# laminadora.net
KiCad netlist of a schematic drawn in EAGLE
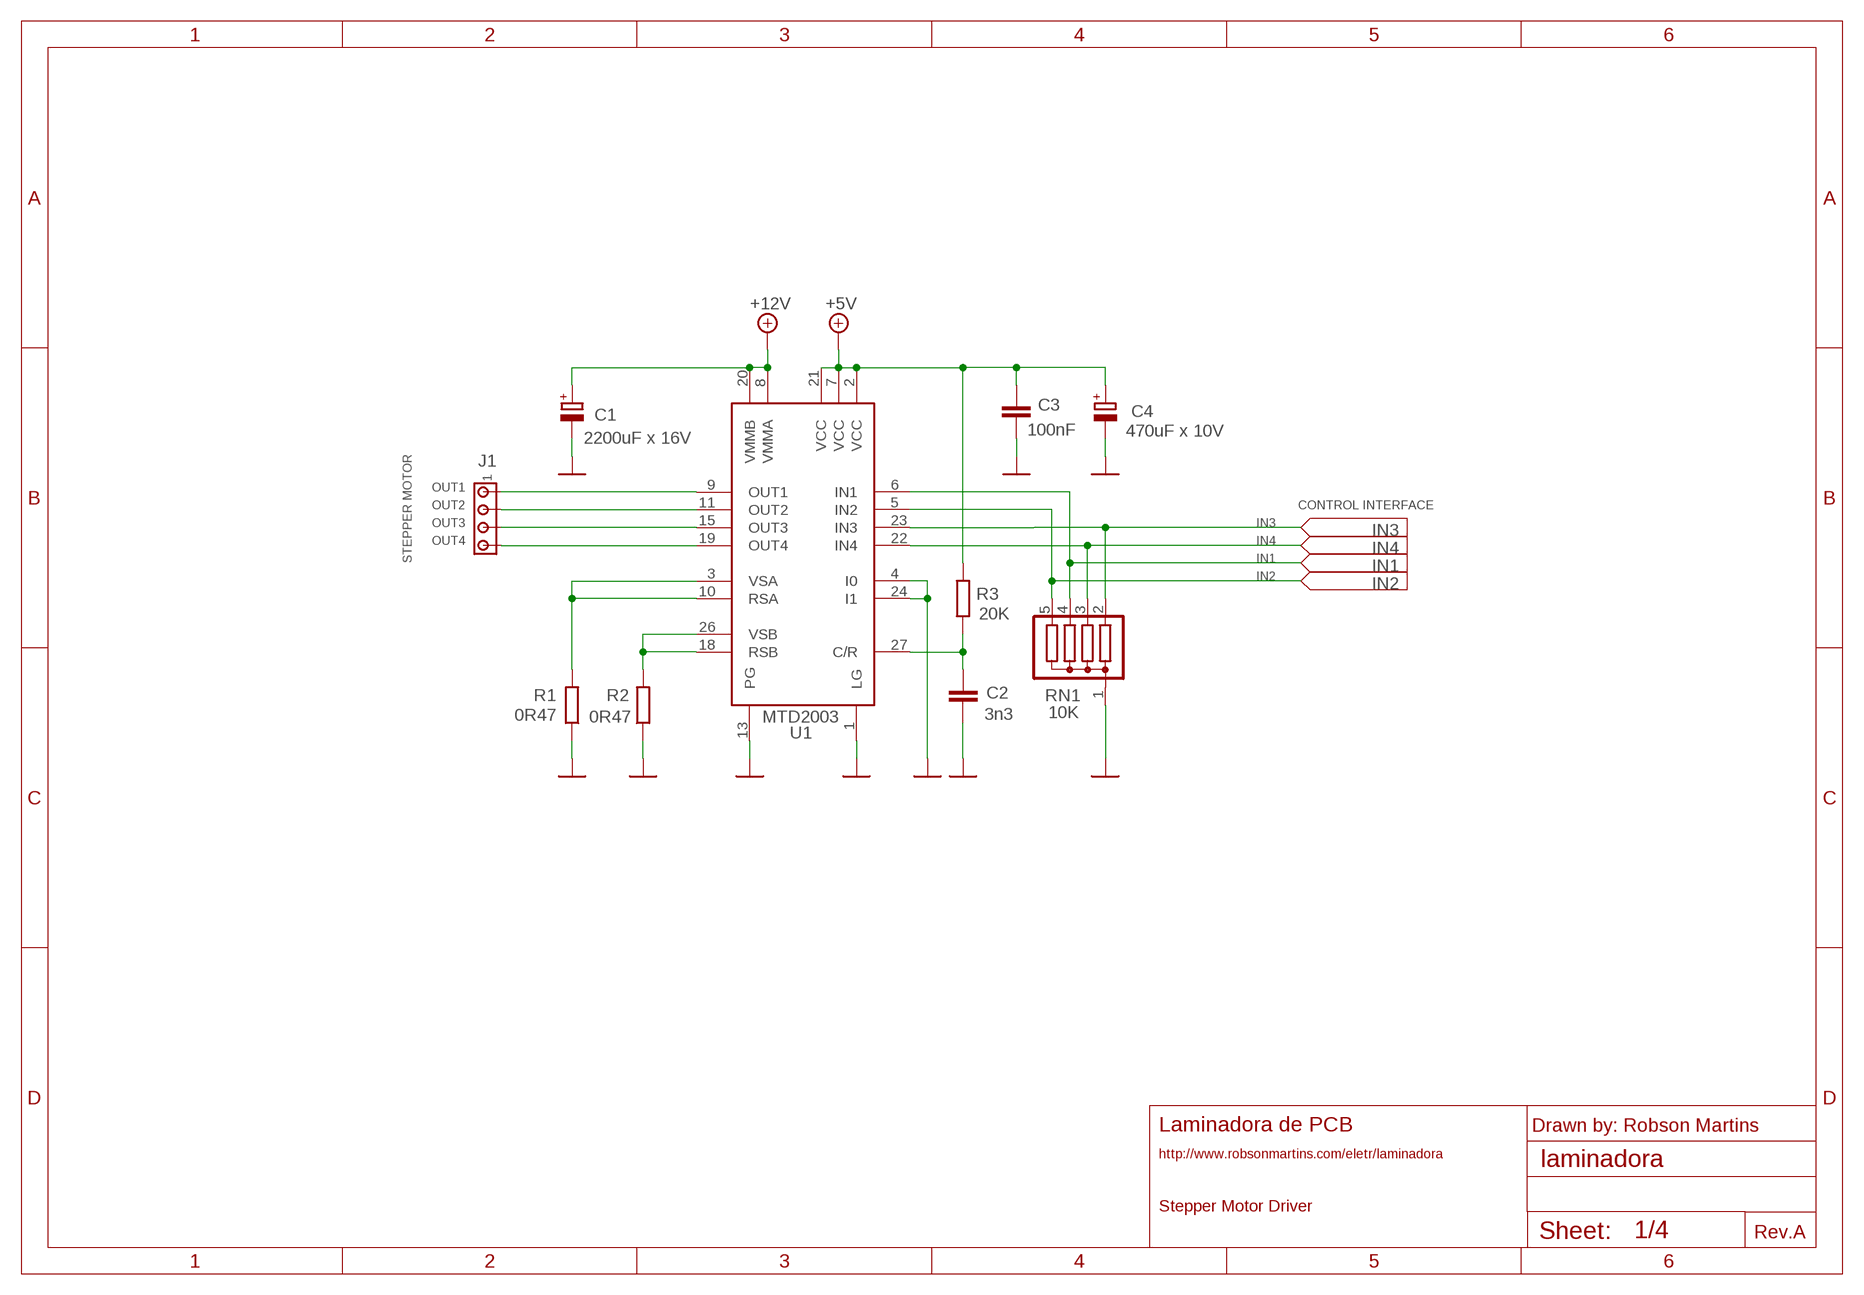
[diagram p0: schematic, sheet 1]
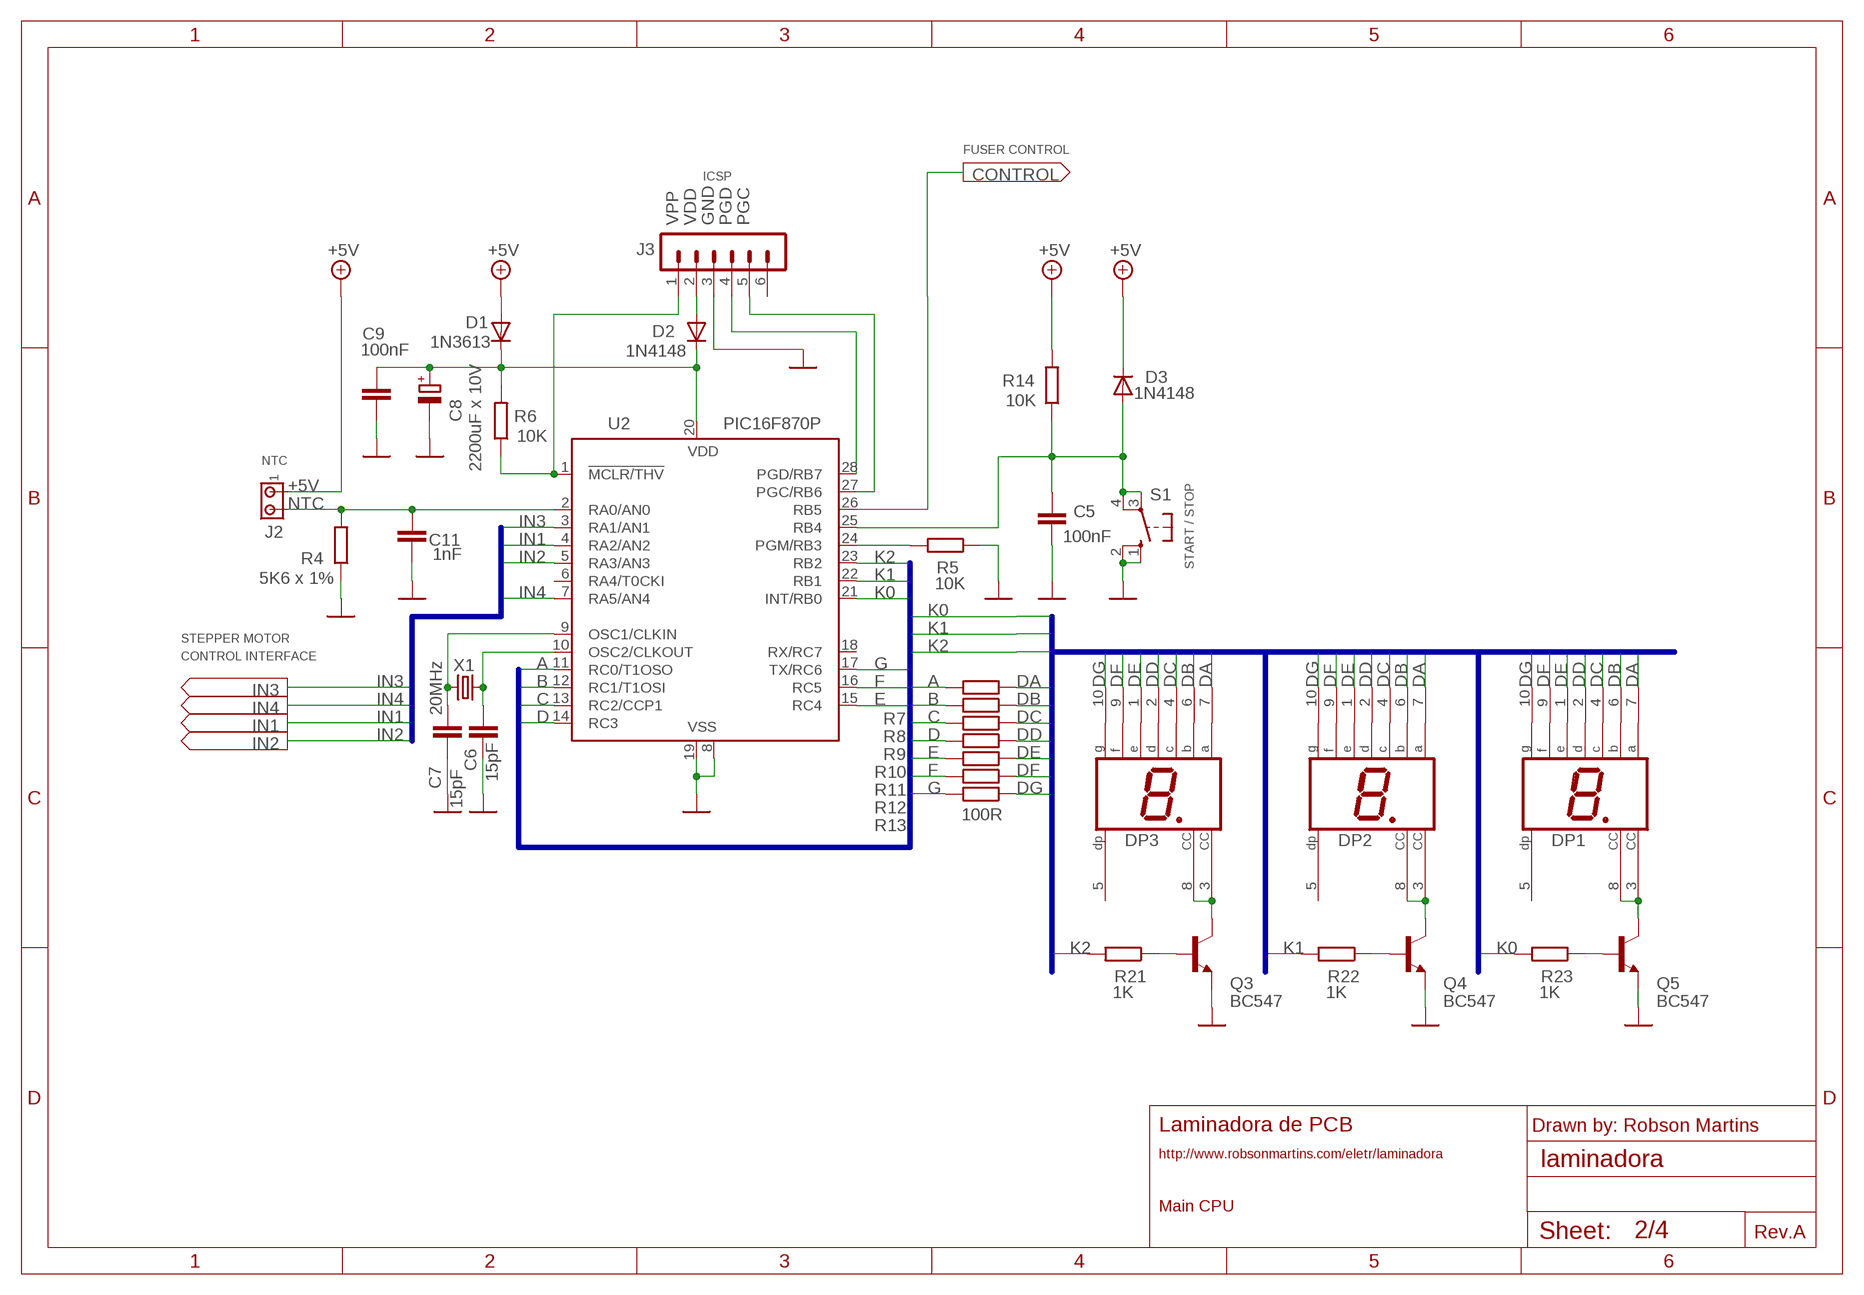
[diagram p1: schematic, sheet 2]
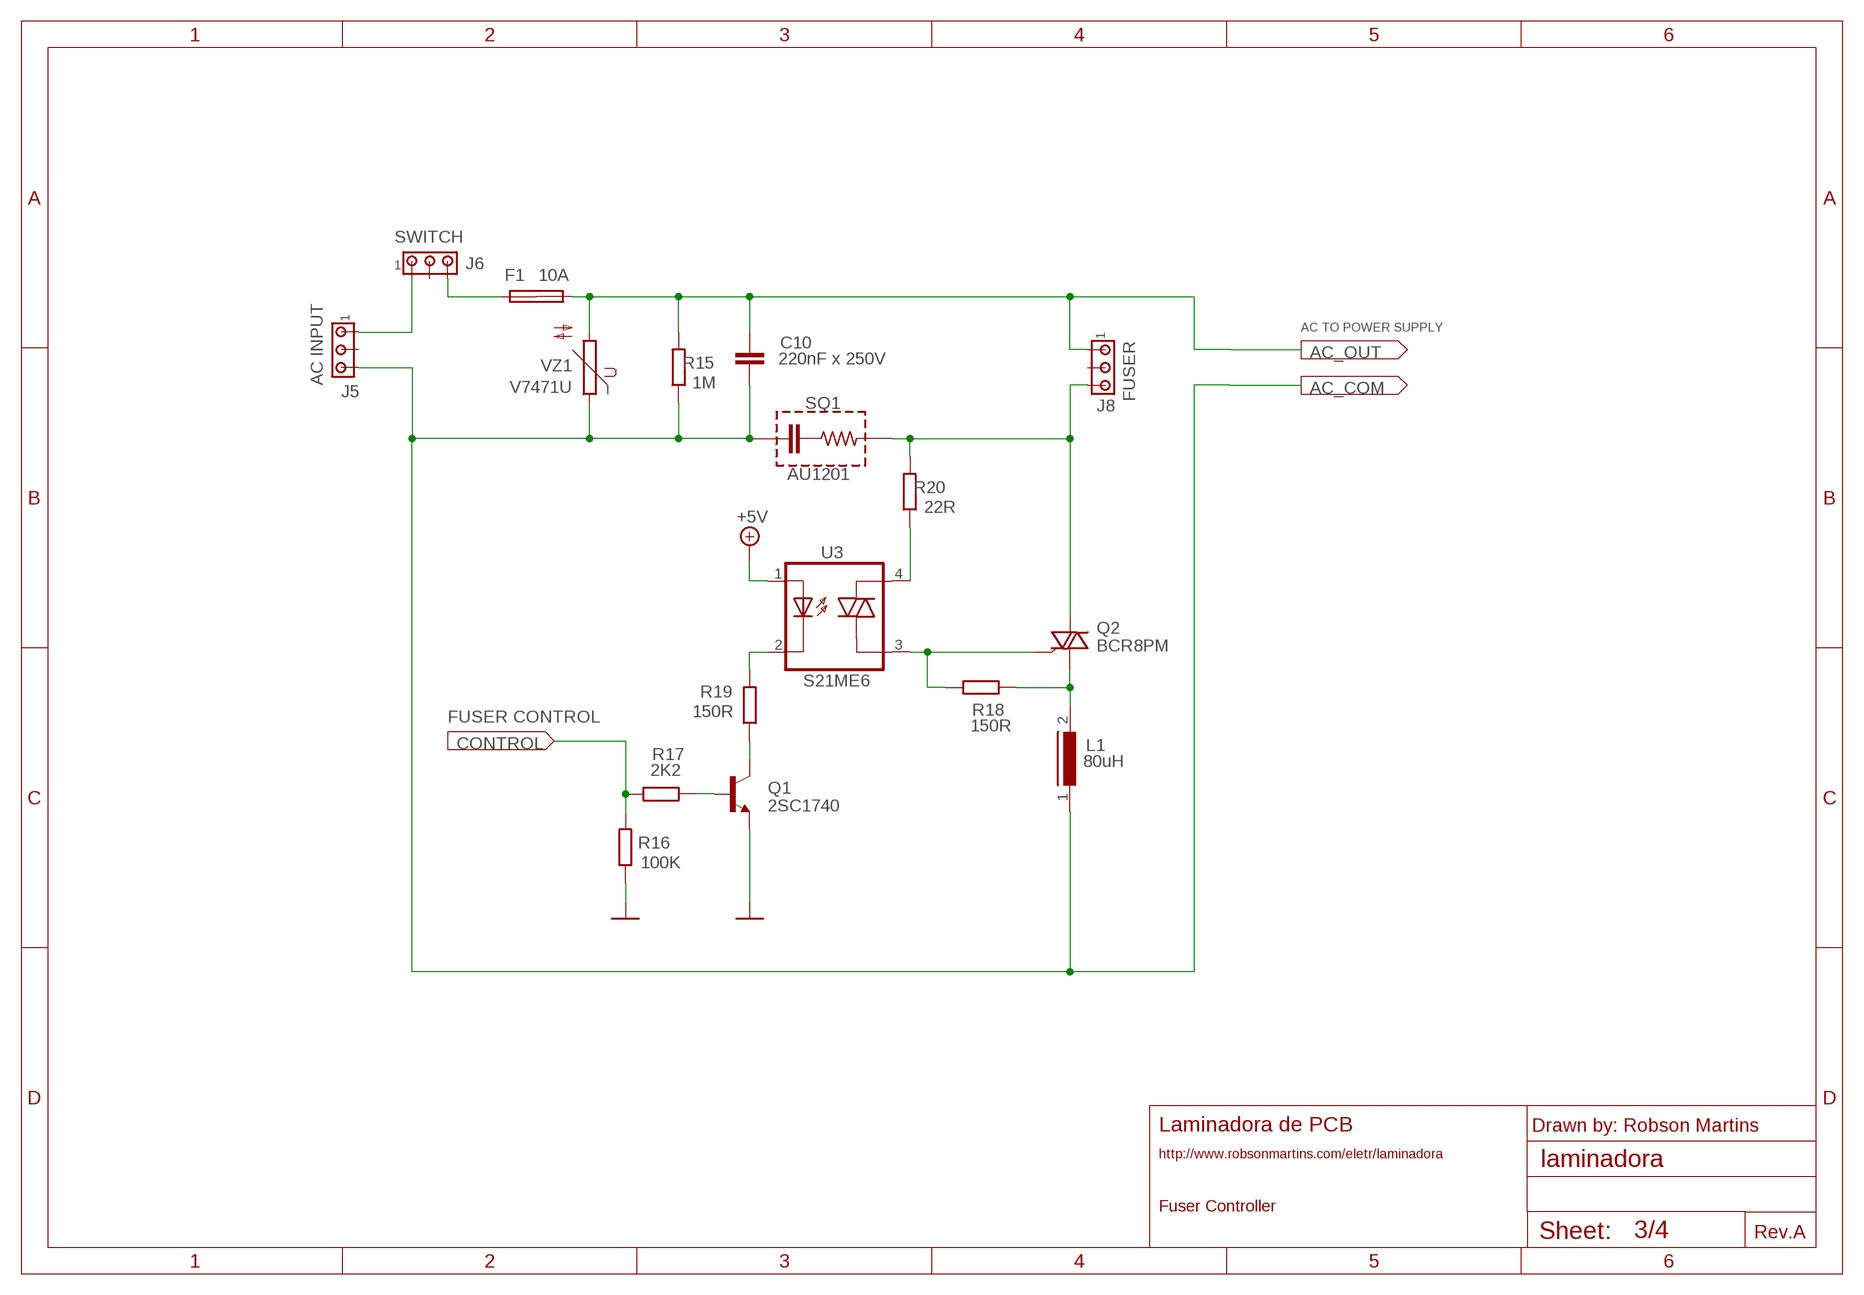
[diagram p2: schematic, sheet 3]
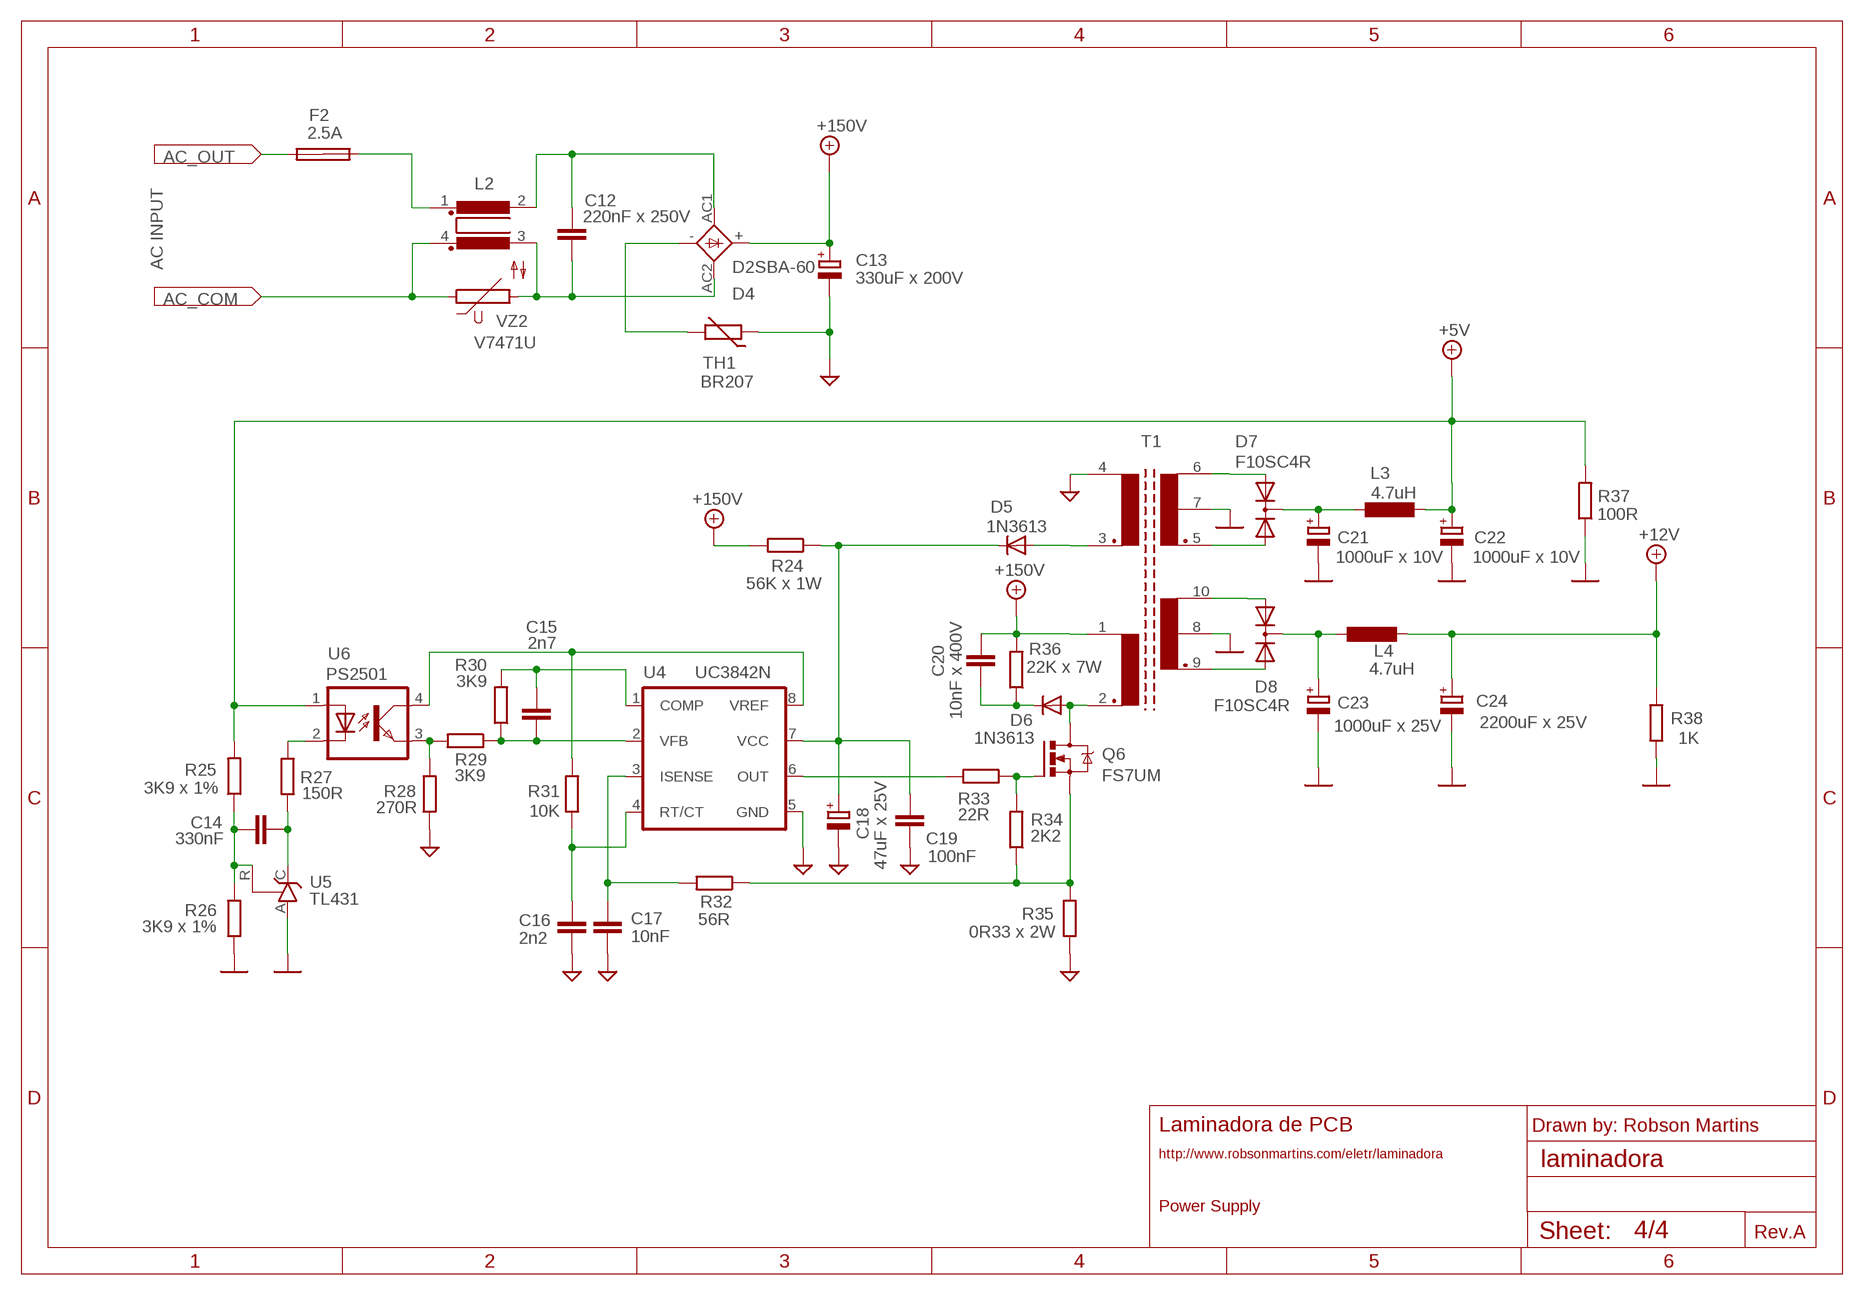
[diagram p3: schematic, sheet 4]

(export (version "E")
  (design (tool "Eeschema 10.0.6"))
  (components
    (comp (ref "C5")
      (value "100nF")
      (footprint "eagle-import:C050-025X075")
      (libsource (lib "eagle-import") (part "C-EU050-025X075"))
    )
    (comp (ref "C6")
      (value "15pF")
      (footprint "eagle-import:C025-025X050")
      (libsource (lib "eagle-import") (part "C-EU025-025X050"))
    )
    (comp (ref "C7")
      (value "15pF")
      (footprint "eagle-import:C025-025X050")
      (libsource (lib "eagle-import") (part "C-EU025-025X050"))
    )
    (comp (ref "C8")
      (value "2200uF x 10V")
      (footprint "eagle-import:E5-13")
      (libsource (lib "eagle-import") (part "CPOL-EUE5-13"))
    )
    (comp (ref "C9")
      (value "100nF")
      (footprint "eagle-import:C050-025X075")
      (libsource (lib "eagle-import") (part "C-EU050-025X075"))
    )
    (comp (ref "C11")
      (value "1nF")
      (footprint "eagle-import:C025-025X050")
      (libsource (lib "eagle-import") (part "C-EU025-025X050"))
    )
    (comp (ref "D1")
      (value "1N3613")
      (footprint "eagle-import:DO35-7")
      (libsource (lib "eagle-import") (part "1N4148DO35-7"))
    )
    (comp (ref "D2")
      (value "1N4148")
      (footprint "eagle-import:DO35-7")
      (libsource (lib "eagle-import") (part "1N4148DO35-7"))
    )
    (comp (ref "D3")
      (value "1N4148")
      (footprint "eagle-import:DO35-7")
      (libsource (lib "eagle-import") (part "1N4148DO35-7"))
    )
    (comp (ref "DP1")
      (value "HD-H103")
      (footprint "eagle-import:HDSP-M")
      (libsource (lib "eagle-import") (part "HD-H103"))
    )
    (comp (ref "DP2")
      (value "HD-H103")
      (footprint "eagle-import:HDSP-M")
      (libsource (lib "eagle-import") (part "HD-H103"))
    )
    (comp (ref "DP3")
      (value "HD-H103")
      (footprint "eagle-import:HDSP-M")
      (libsource (lib "eagle-import") (part "HD-H103"))
    )
    (comp (ref "J2")
      (value "A20-04")
      (footprint "eagle-import:10X02MTA")
      (libsource (lib "eagle-import") (part "MTA02-100"))
    )
    (comp (ref "J3")
      (value "MA06-1")
      (footprint "eagle-import:MA06-1")
      (libsource (lib "eagle-import") (part "MA06-1"))
    )
    (comp (ref "Q3")
      (value "BC547")
      (footprint "eagle-import:TO92")
      (libsource (lib "eagle-import") (part "BC547"))
    )
    (comp (ref "Q4")
      (value "BC547")
      (footprint "eagle-import:TO92")
      (libsource (lib "eagle-import") (part "BC547"))
    )
    (comp (ref "Q5")
      (value "BC547")
      (footprint "eagle-import:TO92")
      (libsource (lib "eagle-import") (part "BC547"))
    )
    (comp (ref "R4")
      (value "5K6 x 1%")
      (footprint "eagle-import:0207_10")
      (libsource (lib "eagle-import") (part "R-EU_0207/10"))
    )
    (comp (ref "R5")
      (value "10K")
      (footprint "eagle-import:0207_10")
      (libsource (lib "eagle-import") (part "R-EU_0207/10"))
    )
    (comp (ref "R6")
      (value "10K")
      (footprint "eagle-import:0207_10")
      (libsource (lib "eagle-import") (part "R-EU_0207/10"))
    )
    (comp (ref "R7")
      (value "100R")
      (footprint "eagle-import:0207_10")
      (libsource (lib "eagle-import") (part "R-EU_0207/10"))
    )
    (comp (ref "R8")
      (value "100R")
      (footprint "eagle-import:0207_10")
      (libsource (lib "eagle-import") (part "R-EU_0207/10"))
    )
    (comp (ref "R9")
      (value "100R")
      (footprint "eagle-import:0207_10")
      (libsource (lib "eagle-import") (part "R-EU_0207/10"))
    )
    (comp (ref "R10")
      (value "100R")
      (footprint "eagle-import:0207_10")
      (libsource (lib "eagle-import") (part "R-EU_0207/10"))
    )
    (comp (ref "R11")
      (value "100R")
      (footprint "eagle-import:0207_10")
      (libsource (lib "eagle-import") (part "R-EU_0207/10"))
    )
    (comp (ref "R12")
      (value "100R")
      (footprint "eagle-import:0207_10")
      (libsource (lib "eagle-import") (part "R-EU_0207/10"))
    )
    (comp (ref "R13")
      (value "100R")
      (footprint "eagle-import:0207_10")
      (libsource (lib "eagle-import") (part "R-EU_0207/10"))
    )
    (comp (ref "R14")
      (value "10K")
      (footprint "eagle-import:0207_10")
      (libsource (lib "eagle-import") (part "R-EU_0207/10"))
    )
    (comp (ref "R21")
      (value "1K")
      (footprint "eagle-import:0207_10")
      (libsource (lib "eagle-import") (part "R-EU_0207/10"))
    )
    (comp (ref "R22")
      (value "1K")
      (footprint "eagle-import:0207_10")
      (libsource (lib "eagle-import") (part "R-EU_0207/10"))
    )
    (comp (ref "R23")
      (value "1K")
      (footprint "eagle-import:0207_10")
      (libsource (lib "eagle-import") (part "R-EU_0207/10"))
    )
    (comp (ref "S1")
      (value "10-XX")
      (footprint "eagle-import:B3F-10XX")
      (fields (field (name "MPN") "B3F-1000"))
      (libsource (lib "eagle-import") (part "10-XX"))
    )
    (comp (ref "U2")
      (value "PIC16F870P")
      (footprint "eagle-import:DIL28-3")
      (fields (field (name "MF") "MICROCHIP") (field (name "MPN") "PIC16F870-I/SP"))
      (libsource (lib "eagle-import") (part "PIC16870PF"))
    )
    (comp (ref "X1")
      (value "20MHz")
      (footprint "eagle-import:HC49U-V")
      (libsource (lib "eagle-import") (part "CRYSTALHC49U-V"))
    )
    (comp (ref "C12")
      (value "220nF x 250V")
      (footprint "eagle-import:C225-108X268")
      (libsource (lib "eagle-import") (part "C-EU225-108X268"))
    )
    (comp (ref "C13")
      (value "330uF x 200V")
      (footprint "eagle-import:EB22,5D")
      (libsource (lib "eagle-import") (part "CPOL-EUE10-22.5"))
    )
    (comp (ref "C14")
      (value "330nF")
      (footprint "eagle-import:C075-042X103")
      (libsource (lib "eagle-import") (part "C-EU075-042X103"))
    )
    (comp (ref "C15")
      (value "2n7")
      (footprint "eagle-import:C050-030X075")
      (libsource (lib "eagle-import") (part "C-EU050-030X075"))
    )
    (comp (ref "C16")
      (value "2n2")
      (footprint "eagle-import:C050-030X075")
      (libsource (lib "eagle-import") (part "C-EU050-030X075"))
    )
    (comp (ref "C17")
      (value "10nF")
      (footprint "eagle-import:C050-030X075")
      (libsource (lib "eagle-import") (part "C-EU050-030X075"))
    )
    (comp (ref "C18")
      (value "47uF x 25V")
      (footprint "eagle-import:E5-6")
      (libsource (lib "eagle-import") (part "CPOL-EUE5-6"))
    )
    (comp (ref "C19")
      (value "100nF")
      (footprint "eagle-import:C050-030X075")
      (libsource (lib "eagle-import") (part "C-EU050-030X075"))
    )
    (comp (ref "C20")
      (value "10nF x 400V")
      (footprint "eagle-import:C102-043X133")
      (libsource (lib "eagle-import") (part "C-EU102-043X133"))
    )
    (comp (ref "C21")
      (value "1000uF x 10V")
      (footprint "eagle-import:E5-10,5")
      (libsource (lib "eagle-import") (part "CPOL-EUE5-10.5"))
    )
    (comp (ref "C22")
      (value "1000uF x 10V")
      (footprint "eagle-import:E5-10,5")
      (libsource (lib "eagle-import") (part "CPOL-EUE5-10.5"))
    )
    (comp (ref "C23")
      (value "1000uF x 25V")
      (footprint "eagle-import:E5-13")
      (libsource (lib "eagle-import") (part "CPOL-EUE5-13"))
    )
    (comp (ref "C24")
      (value "2200uF x 25V")
      (footprint "eagle-import:E5-13")
      (libsource (lib "eagle-import") (part "CPOL-EUE5-13"))
    )
    (comp (ref "D4")
      (value "D2SBA-60")
      (footprint "eagle-import:FBU4")
      (libsource (lib "eagle-import") (part "FBU4"))
    )
    (comp (ref "D5")
      (value "1N3613")
      (footprint "eagle-import:DO35-7")
      (libsource (lib "eagle-import") (part "1N4148DO35-7"))
    )
    (comp (ref "D6")
      (value "1N3613")
      (footprint "eagle-import:DO35-7")
      (libsource (lib "eagle-import") (part "1N4148DO35-7"))
    )
    (comp (ref "D7")
      (value "F10SC4R")
      (footprint "eagle-import:TO220ABS")
      (libsource (lib "eagle-import") (part "FEP16AT"))
    )
    (comp (ref "D8")
      (value "F10SC4R")
      (footprint "eagle-import:TO220ABS")
      (libsource (lib "eagle-import") (part "FEP16AT"))
    )
    (comp (ref "F2")
      (value "2.5A")
      (footprint "eagle-import:SHK20L")
      (libsource (lib "eagle-import") (part "SHK20L"))
    )
    (comp (ref "L2")
      (value "MFE")
      (footprint "eagle-import:MFE")
      (libsource (lib "eagle-import") (part "MFE"))
    )
    (comp (ref "L3")
      (value "4.7uH")
      (footprint "eagle-import:6000-XXXX-RC")
      (libsource (lib "eagle-import") (part "L-EU6000-XXX-RC"))
    )
    (comp (ref "L4")
      (value "4.7uH")
      (footprint "eagle-import:6000-XXXX-RC")
      (libsource (lib "eagle-import") (part "L-EU6000-XXX-RC"))
    )
    (comp (ref "Q6")
      (value "FS7UM")
      (footprint "eagle-import:TO220BV")
      (libsource (lib "eagle-import") (part "IRF540"))
    )
    (comp (ref "R24")
      (value "56K x 1W")
      (footprint "eagle-import:0309_12")
      (libsource (lib "eagle-import") (part "R-EU_0309/12"))
    )
    (comp (ref "R25")
      (value "3K9 x 1%")
      (footprint "eagle-import:0207_10")
      (libsource (lib "eagle-import") (part "R-EU_0207/10"))
    )
    (comp (ref "R26")
      (value "3K9 x 1%")
      (footprint "eagle-import:0207_10")
      (libsource (lib "eagle-import") (part "R-EU_0207/10"))
    )
    (comp (ref "R27")
      (value "150R")
      (footprint "eagle-import:0207_10")
      (libsource (lib "eagle-import") (part "R-EU_0207/10"))
    )
    (comp (ref "R28")
      (value "270R")
      (footprint "eagle-import:0207_10")
      (libsource (lib "eagle-import") (part "R-EU_0207/10"))
    )
    (comp (ref "R29")
      (value "3K9")
      (footprint "eagle-import:0207_10")
      (libsource (lib "eagle-import") (part "R-EU_0207/10"))
    )
    (comp (ref "R30")
      (value "3K9")
      (footprint "eagle-import:0207_10")
      (libsource (lib "eagle-import") (part "R-EU_0207/10"))
    )
    (comp (ref "R31")
      (value "10K")
      (footprint "eagle-import:0207_10")
      (libsource (lib "eagle-import") (part "R-EU_0207/10"))
    )
    (comp (ref "R32")
      (value "56R")
      (footprint "eagle-import:0207_10")
      (libsource (lib "eagle-import") (part "R-EU_0207/10"))
    )
    (comp (ref "R33")
      (value "22R")
      (footprint "eagle-import:0207_10")
      (libsource (lib "eagle-import") (part "R-EU_0207/10"))
    )
    (comp (ref "R34")
      (value "2K2")
      (footprint "eagle-import:0207_10")
      (libsource (lib "eagle-import") (part "R-EU_0207/10"))
    )
    (comp (ref "R35")
      (value "0R33 x 2W")
      (footprint "eagle-import:0411_15")
      (libsource (lib "eagle-import") (part "R-EU_0411/15"))
    )
    (comp (ref "R36")
      (value "22K x 7W")
      (footprint "eagle-import:0617V")
      (libsource (lib "eagle-import") (part "R-EU_0617/5V"))
    )
    (comp (ref "R37")
      (value "100R")
      (footprint "eagle-import:0207_10")
      (libsource (lib "eagle-import") (part "R-EU_0207/10"))
    )
    (comp (ref "R38")
      (value "1K")
      (footprint "eagle-import:0207_10")
      (libsource (lib "eagle-import") (part "R-EU_0207/10"))
    )
    (comp (ref "T1")
      (value "SK69ABD2")
      (footprint "eagle-import:SK69ABD2")
      (libsource (lib "eagle-import") (part "SK69ABD2"))
    )
    (comp (ref "TH1")
      (value "BR207")
      (footprint "eagle-import:R-7,5")
      (libsource (lib "eagle-import") (part "THERMISTOR-7,5"))
    )
    (comp (ref "U4")
      (value "UC3842N")
      (footprint "eagle-import:DIL08")
      (libsource (lib "eagle-import") (part "UC384N2"))
    )
    (comp (ref "U5")
      (value "TL431")
      (footprint "eagle-import:TO92-CLP")
      (libsource (lib "eagle-import") (part "TL431CLP"))
    )
    (comp (ref "U6")
      (value "PS2501")
      (footprint "eagle-import:DIL04")
      (fields (field (name "MPN") "PC817X4J000F"))
      (libsource (lib "eagle-import") (part "PC817"))
    )
    (comp (ref "VZ2")
      (value "V7471U")
      (footprint "eagle-import:S05K17")
      (libsource (lib "eagle-import") (part "S05K17"))
    )
    (comp (ref "C1")
      (value "2200uF x 16V")
      (footprint "eagle-import:E5-13")
      (libsource (lib "eagle-import") (part "CPOL-EUE5-13"))
    )
    (comp (ref "C2")
      (value "3n3")
      (footprint "eagle-import:C050-025X075")
      (libsource (lib "eagle-import") (part "C-EU050-025X075"))
    )
    (comp (ref "C3")
      (value "100nF")
      (footprint "eagle-import:C050-025X075")
      (libsource (lib "eagle-import") (part "C-EU050-025X075"))
    )
    (comp (ref "C4")
      (value "470uF x 10V")
      (footprint "eagle-import:E5-8,5")
      (libsource (lib "eagle-import") (part "CPOL-EUE5-8.5"))
    )
    (comp (ref "J1")
      (value "A20-04")
      (footprint "eagle-import:A20-04")
      (libsource (lib "eagle-import") (part "A20-04"))
    )
    (comp (ref "R1")
      (value "0R47")
      (footprint "eagle-import:0309_12")
      (libsource (lib "eagle-import") (part "R-EU_0309/12"))
    )
    (comp (ref "R2")
      (value "0R47")
      (footprint "eagle-import:0309_12")
      (libsource (lib "eagle-import") (part "R-EU_0309/12"))
    )
    (comp (ref "R3")
      (value "20K")
      (footprint "eagle-import:0207_10")
      (libsource (lib "eagle-import") (part "R-EU_0207/10"))
    )
    (comp (ref "RN1")
      (value "10K")
      (footprint "eagle-import:SIL5")
      (libsource (lib "eagle-import") (part "G04R"))
    )
    (comp (ref "U1")
      (value "MTD2003")
      (footprint "eagle-import:ZIP27SINK")
      (libsource (lib "eagle-import") (part "MTD2003ZIP27SINK"))
    )
    (comp (ref "C10")
      (value "220nF x 250V")
      (footprint "eagle-import:C225-108X268")
      (libsource (lib "eagle-import") (part "C-EU225-108X268"))
    )
    (comp (ref "F1")
      (value "10A")
      (footprint "eagle-import:SHK20L")
      (libsource (lib "eagle-import") (part "SHK20L"))
    )
    (comp (ref "J5")
      (value "794681-2")
      (footprint "eagle-import:1X3MTA")
      (libsource (lib "eagle-import") (part "MTA03-156"))
    )
    (comp (ref "J6")
      (value "794681-2")
      (footprint "eagle-import:1X3MTA")
      (libsource (lib "eagle-import") (part "MTA03-156"))
    )
    (comp (ref "J8")
      (value "794681-2")
      (footprint "eagle-import:1X3MTA")
      (libsource (lib "eagle-import") (part "MTA03-156"))
    )
    (comp (ref "L1")
      (value "80uH")
      (footprint "eagle-import:A26GFC")
      (libsource (lib "eagle-import") (part "A26GFC"))
    )
    (comp (ref "Q1")
      (value "2SC1740")
      (footprint "eagle-import:TO92-ECB")
      (libsource (lib "eagle-import") (part "2SC1740"))
    )
    (comp (ref "Q2")
      (value "BCR8PM")
      (footprint "eagle-import:TO220BVSINK")
      (libsource (lib "eagle-import") (part "BCR8PMTO220BVSINK"))
    )
    (comp (ref "R15")
      (value "1M")
      (footprint "eagle-import:0207_10")
      (libsource (lib "eagle-import") (part "R-EU_0207/10"))
    )
    (comp (ref "R16")
      (value "100K")
      (footprint "eagle-import:0207_10")
      (libsource (lib "eagle-import") (part "R-EU_0207/10"))
    )
    (comp (ref "R17")
      (value "2K2")
      (footprint "eagle-import:0207_10")
      (libsource (lib "eagle-import") (part "R-EU_0207/10"))
    )
    (comp (ref "R18")
      (value "150R")
      (footprint "eagle-import:0207_10")
      (libsource (lib "eagle-import") (part "R-EU_0207/10"))
    )
    (comp (ref "R19")
      (value "150R")
      (footprint "eagle-import:0207_10")
      (libsource (lib "eagle-import") (part "R-EU_0207/10"))
    )
    (comp (ref "R20")
      (value "22R")
      (footprint "eagle-import:0207_10")
      (libsource (lib "eagle-import") (part "R-EU_0207/10"))
    )
    (comp (ref "SQ1")
      (value "AU1201")
      (footprint "eagle-import:AU")
      (libsource (lib "eagle-import") (part "AU1201"))
    )
    (comp (ref "U3")
      (value "S21ME6")
      (footprint "eagle-import:DIL4")
      (libsource (lib "eagle-import") (part "S21ME6"))
    )
    (comp (ref "VZ1")
      (value "V7471U")
      (footprint "eagle-import:S05K17")
      (libsource (lib "eagle-import") (part "S05K17"))
    )
  )
  (nets
    (net (code "1") (name "+5V") (class "Default")
      (node (ref "C22") (pin "+") (pinfunction "+_+") (pintype "passive"))
      (node (ref "C3") (pin "1") (pinfunction "1_1") (pintype "passive"))
      (node (ref "C4") (pin "+") (pinfunction "+_+") (pintype "passive"))
      (node (ref "D1") (pin "A") (pinfunction "A_A") (pintype "passive"))
      (node (ref "D3") (pin "C") (pinfunction "C_C") (pintype "passive"))
      (node (ref "J2") (pin "1") (pinfunction "1_1") (pintype "passive"))
      (node (ref "L3") (pin "2") (pinfunction "2_2") (pintype "passive"))
      (node (ref "R14") (pin "2") (pinfunction "2_2") (pintype "passive"))
      (node (ref "R25") (pin "2") (pinfunction "2_2") (pintype "passive"))
      (node (ref "R3") (pin "2") (pinfunction "2_2") (pintype "passive"))
      (node (ref "R37") (pin "2") (pinfunction "2_2") (pintype "passive"))
      (node (ref "U1") (pin "2") (pinfunction "VCC_2") (pintype "power_in"))
      (node (ref "U1") (pin "21") (pinfunction "VCC_21") (pintype "power_in"))
      (node (ref "U1") (pin "7") (pinfunction "VCC_7") (pintype "power_in"))
      (node (ref "U3") (pin "1") (pinfunction "A_1") (pintype "passive"))
      (node (ref "U6") (pin "1") (pinfunction "A_1") (pintype "passive"))
    )
    (net (code "2") (name "+12V") (class "Default")
      (node (ref "C1") (pin "+") (pinfunction "+_+") (pintype "passive"))
      (node (ref "C24") (pin "+") (pinfunction "+_+") (pintype "passive"))
      (node (ref "L4") (pin "2") (pinfunction "2_2") (pintype "passive"))
      (node (ref "R38") (pin "2") (pinfunction "2_2") (pintype "passive"))
      (node (ref "U1") (pin "20") (pinfunction "VMMB_20") (pintype "power_in"))
      (node (ref "U1") (pin "8") (pinfunction "VMMA_8") (pintype "power_in"))
    )
    (net (code "3") (name "+150V") (class "Default")
      (node (ref "C13") (pin "+") (pinfunction "+_+") (pintype "passive"))
      (node (ref "C20") (pin "1") (pinfunction "1_1") (pintype "passive"))
      (node (ref "D4") (pin "+") (pinfunction "+_+") (pintype "passive"))
      (node (ref "R24") (pin "2") (pinfunction "2_2") (pintype "passive"))
      (node (ref "R36") (pin "2") (pinfunction "2_2") (pintype "passive"))
      (node (ref "T1") (pin "1") (pinfunction "3_1") (pintype "passive"))
    )
    (net (code "4") (name "A") (class "Default")
      (node (ref "R7") (pin "2") (pinfunction "2_2") (pintype "passive"))
      (node (ref "U2") (pin "11") (pinfunction "RC0/T1OSO_11") (pintype "bidirectional"))
    )
    (net (code "5") (name "AC_COM") (class "Default")
      (node (ref "C10") (pin "2") (pinfunction "2_2") (pintype "passive"))
      (node (ref "J5") (pin "3") (pinfunction "3_3") (pintype "passive"))
      (node (ref "L1") (pin "1") (pinfunction "1_1") (pintype "passive"))
      (node (ref "L2") (pin "4") (pinfunction "3_4") (pintype "passive"))
      (node (ref "R15") (pin "1") (pinfunction "1_1") (pintype "passive"))
      (node (ref "SQ1") (pin "1") (pinfunction "2_1") (pintype "passive"))
      (node (ref "VZ1") (pin "1") (pinfunction "1_1") (pintype "passive"))
      (node (ref "VZ2") (pin "1") (pinfunction "1_1") (pintype "passive"))
    )
    (net (code "6") (name "AC_OUT") (class "Default")
      (node (ref "C10") (pin "1") (pinfunction "1_1") (pintype "passive"))
      (node (ref "F1") (pin "2A") (pinfunction "2A_2A") (pintype "passive"))
      (node (ref "F2") (pin "1A") (pinfunction "1A_1A") (pintype "passive"))
      (node (ref "J8") (pin "1") (pinfunction "1_1") (pintype "passive"))
      (node (ref "R15") (pin "2") (pinfunction "2_2") (pintype "passive"))
      (node (ref "VZ1") (pin "2") (pinfunction "2_2") (pintype "passive"))
    )
    (net (code "7") (name "AGND") (class "Default")
      (node (ref "C13") (pin "-") (pinfunction "-_-") (pintype "passive"))
      (node (ref "C16") (pin "2") (pinfunction "2_2") (pintype "passive"))
      (node (ref "C17") (pin "2") (pinfunction "2_2") (pintype "passive"))
      (node (ref "C18") (pin "-") (pinfunction "-_-") (pintype "passive"))
      (node (ref "C19") (pin "2") (pinfunction "2_2") (pintype "passive"))
      (node (ref "R28") (pin "1") (pinfunction "1_1") (pintype "passive"))
      (node (ref "R35") (pin "1") (pinfunction "1_1") (pintype "passive"))
      (node (ref "T1") (pin "4") (pinfunction "1_4") (pintype "passive"))
      (node (ref "TH1") (pin "1") (pinfunction "1_1") (pintype "passive"))
      (node (ref "U4") (pin "5") (pinfunction "GND_5") (pintype "power_in"))
    )
    (net (code "8") (name "B") (class "Default")
      (node (ref "R8") (pin "2") (pinfunction "2_2") (pintype "passive"))
      (node (ref "U2") (pin "12") (pinfunction "RC1/T1OSI_12") (pintype "bidirectional"))
    )
    (net (code "9") (name "C") (class "Default")
      (node (ref "R9") (pin "2") (pinfunction "2_2") (pintype "passive"))
      (node (ref "U2") (pin "13") (pinfunction "RC2/CCP1_13") (pintype "bidirectional"))
    )
    (net (code "10") (name "CONTROL") (class "Default")
      (node (ref "R16") (pin "2") (pinfunction "2_2") (pintype "passive"))
      (node (ref "R17") (pin "2") (pinfunction "2_2") (pintype "passive"))
      (node (ref "U2") (pin "26") (pinfunction "RB5_26") (pintype "bidirectional"))
    )
    (net (code "11") (name "D") (class "Default")
      (node (ref "R10") (pin "2") (pinfunction "2_2") (pintype "passive"))
      (node (ref "U2") (pin "14") (pinfunction "RC3_14") (pintype "bidirectional"))
    )
    (net (code "12") (name "DA") (class "Default")
      (node (ref "DP1") (pin "7") (pinfunction "A_7") (pintype "passive"))
      (node (ref "DP2") (pin "7") (pinfunction "A_7") (pintype "passive"))
      (node (ref "DP3") (pin "7") (pinfunction "A_7") (pintype "passive"))
      (node (ref "R7") (pin "1") (pinfunction "1_1") (pintype "passive"))
    )
    (net (code "13") (name "DB") (class "Default")
      (node (ref "DP1") (pin "6") (pinfunction "B_6") (pintype "passive"))
      (node (ref "DP2") (pin "6") (pinfunction "B_6") (pintype "passive"))
      (node (ref "DP3") (pin "6") (pinfunction "B_6") (pintype "passive"))
      (node (ref "R8") (pin "1") (pinfunction "1_1") (pintype "passive"))
    )
    (net (code "14") (name "DC") (class "Default")
      (node (ref "DP1") (pin "4") (pinfunction "C_4") (pintype "passive"))
      (node (ref "DP2") (pin "4") (pinfunction "C_4") (pintype "passive"))
      (node (ref "DP3") (pin "4") (pinfunction "C_4") (pintype "passive"))
      (node (ref "R9") (pin "1") (pinfunction "1_1") (pintype "passive"))
    )
    (net (code "15") (name "DD") (class "Default")
      (node (ref "DP1") (pin "2") (pinfunction "D_2") (pintype "passive"))
      (node (ref "DP2") (pin "2") (pinfunction "D_2") (pintype "passive"))
      (node (ref "DP3") (pin "2") (pinfunction "D_2") (pintype "passive"))
      (node (ref "R10") (pin "1") (pinfunction "1_1") (pintype "passive"))
    )
    (net (code "16") (name "DE") (class "Default")
      (node (ref "DP1") (pin "1") (pinfunction "E_1") (pintype "passive"))
      (node (ref "DP2") (pin "1") (pinfunction "E_1") (pintype "passive"))
      (node (ref "DP3") (pin "1") (pinfunction "E_1") (pintype "passive"))
      (node (ref "R11") (pin "1") (pinfunction "1_1") (pintype "passive"))
    )
    (net (code "17") (name "DF") (class "Default")
      (node (ref "DP1") (pin "9") (pinfunction "F_9") (pintype "passive"))
      (node (ref "DP2") (pin "9") (pinfunction "F_9") (pintype "passive"))
      (node (ref "DP3") (pin "9") (pinfunction "F_9") (pintype "passive"))
      (node (ref "R12") (pin "1") (pinfunction "1_1") (pintype "passive"))
    )
    (net (code "18") (name "DG") (class "Default")
      (node (ref "DP1") (pin "10") (pinfunction "G_10") (pintype "passive"))
      (node (ref "DP2") (pin "10") (pinfunction "G_10") (pintype "passive"))
      (node (ref "DP3") (pin "10") (pinfunction "G_10") (pintype "passive"))
      (node (ref "R13") (pin "1") (pinfunction "1_1") (pintype "passive"))
    )
    (net (code "19") (name "E") (class "Default")
      (node (ref "R11") (pin "2") (pinfunction "2_2") (pintype "passive"))
      (node (ref "U2") (pin "15") (pinfunction "RC4_15") (pintype "bidirectional"))
    )
    (net (code "20") (name "F") (class "Default")
      (node (ref "R12") (pin "2") (pinfunction "2_2") (pintype "passive"))
      (node (ref "U2") (pin "16") (pinfunction "RC5_16") (pintype "bidirectional"))
    )
    (net (code "21") (name "G") (class "Default")
      (node (ref "R13") (pin "2") (pinfunction "2_2") (pintype "passive"))
      (node (ref "U2") (pin "17") (pinfunction "TX/RC6_17") (pintype "bidirectional"))
    )
    (net (code "22") (name "GND") (class "Default")
      (node (ref "C1") (pin "-") (pinfunction "-_-") (pintype "passive"))
      (node (ref "C11") (pin "2") (pinfunction "2_2") (pintype "passive"))
      (node (ref "C2") (pin "2") (pinfunction "2_2") (pintype "passive"))
      (node (ref "C21") (pin "-") (pinfunction "-_-") (pintype "passive"))
      (node (ref "C22") (pin "-") (pinfunction "-_-") (pintype "passive"))
      (node (ref "C23") (pin "-") (pinfunction "-_-") (pintype "passive"))
      (node (ref "C24") (pin "-") (pinfunction "-_-") (pintype "passive"))
      (node (ref "C3") (pin "2") (pinfunction "2_2") (pintype "passive"))
      (node (ref "C4") (pin "-") (pinfunction "-_-") (pintype "passive"))
      (node (ref "C5") (pin "2") (pinfunction "2_2") (pintype "passive"))
      (node (ref "C6") (pin "2") (pinfunction "2_2") (pintype "passive"))
      (node (ref "C7") (pin "2") (pinfunction "2_2") (pintype "passive"))
      (node (ref "C8") (pin "-") (pinfunction "-_-") (pintype "passive"))
      (node (ref "C9") (pin "2") (pinfunction "2_2") (pintype "passive"))
      (node (ref "J3") (pin "3") (pinfunction "3_3") (pintype "passive"))
      (node (ref "Q1") (pin "E") (pinfunction "E_E") (pintype "passive"))
      (node (ref "Q3") (pin "1") (pinfunction "E_1") (pintype "passive"))
      (node (ref "Q4") (pin "1") (pinfunction "E_1") (pintype "passive"))
      (node (ref "Q5") (pin "1") (pinfunction "E_1") (pintype "passive"))
      (node (ref "R1") (pin "1") (pinfunction "1_1") (pintype "passive"))
      (node (ref "R16") (pin "1") (pinfunction "1_1") (pintype "passive"))
      (node (ref "R2") (pin "1") (pinfunction "1_1") (pintype "passive"))
      (node (ref "R26") (pin "1") (pinfunction "1_1") (pintype "passive"))
      (node (ref "R37") (pin "1") (pinfunction "1_1") (pintype "passive"))
      (node (ref "R38") (pin "1") (pinfunction "1_1") (pintype "passive"))
      (node (ref "R4") (pin "1") (pinfunction "1_1") (pintype "passive"))
      (node (ref "R5") (pin "1") (pinfunction "1_1") (pintype "passive"))
      (node (ref "RN1") (pin "1") (pinfunction "1_1") (pintype "passive"))
      (node (ref "S1") (pin "1") (pinfunction "S_1") (pintype "passive"))
      (node (ref "S1") (pin "2") (pinfunction "S1_2") (pintype "passive"))
      (node (ref "T1") (pin "7") (pinfunction "9_7") (pintype "passive"))
      (node (ref "T1") (pin "8") (pinfunction "6_8") (pintype "passive"))
      (node (ref "U1") (pin "1") (pinfunction "LG_1") (pintype "power_in"))
      (node (ref "U1") (pin "13") (pinfunction "PG_13") (pintype "power_in"))
      (node (ref "U1") (pin "24") (pinfunction "I1_24") (pintype "input"))
      (node (ref "U1") (pin "4") (pinfunction "I0_4") (pintype "input"))
      (node (ref "U2") (pin "19") (pinfunction "VSS_19") (pintype "power_in"))
      (node (ref "U2") (pin "8") (pinfunction "VSS_8") (pintype "power_in"))
      (node (ref "U5") (pin "A") (pinfunction "A_A") (pintype "passive"))
    )
    (net (code "23") (name "IN1") (class "Default")
      (node (ref "RN1") (pin "4") (pinfunction "4_4") (pintype "passive"))
      (node (ref "U1") (pin "6") (pinfunction "IN1_6") (pintype "input"))
      (node (ref "U2") (pin "4") (pinfunction "RA2/AN2_4") (pintype "bidirectional"))
    )
    (net (code "24") (name "IN2") (class "Default")
      (node (ref "RN1") (pin "5") (pinfunction "5_5") (pintype "passive"))
      (node (ref "U1") (pin "5") (pinfunction "IN2_5") (pintype "input"))
      (node (ref "U2") (pin "5") (pinfunction "RA3/AN3_5") (pintype "bidirectional"))
    )
    (net (code "25") (name "IN3") (class "Default")
      (node (ref "RN1") (pin "2") (pinfunction "2_2") (pintype "passive"))
      (node (ref "U1") (pin "23") (pinfunction "IN3_23") (pintype "input"))
      (node (ref "U2") (pin "3") (pinfunction "RA1/AN1_3") (pintype "bidirectional"))
    )
    (net (code "26") (name "IN4") (class "Default")
      (node (ref "RN1") (pin "3") (pinfunction "3_3") (pintype "passive"))
      (node (ref "U1") (pin "22") (pinfunction "IN4_22") (pintype "input"))
      (node (ref "U2") (pin "7") (pinfunction "RA5/AN4_7") (pintype "bidirectional"))
    )
    (net (code "27") (name "K0") (class "Default")
      (node (ref "R23") (pin "2") (pinfunction "2_2") (pintype "passive"))
      (node (ref "U2") (pin "21") (pinfunction "INT/RB0_21") (pintype "bidirectional"))
    )
    (net (code "28") (name "K1") (class "Default")
      (node (ref "R22") (pin "2") (pinfunction "2_2") (pintype "passive"))
      (node (ref "U2") (pin "22") (pinfunction "RB1_22") (pintype "bidirectional"))
    )
    (net (code "29") (name "K2") (class "Default")
      (node (ref "R21") (pin "2") (pinfunction "2_2") (pintype "passive"))
      (node (ref "U2") (pin "23") (pinfunction "RB2_23") (pintype "bidirectional"))
    )
    (net (code "30") (name "NTC") (class "Default")
      (node (ref "C11") (pin "1") (pinfunction "1_1") (pintype "passive"))
      (node (ref "J2") (pin "2") (pinfunction "2_2") (pintype "passive"))
      (node (ref "R4") (pin "2") (pinfunction "2_2") (pintype "passive"))
      (node (ref "U2") (pin "2") (pinfunction "RA0/AN0_2") (pintype "bidirectional"))
    )
    (net (code "31") (name "Net-(C14-Pad1)") (class "Default")
      (node (ref "C14") (pin "1") (pinfunction "1_1") (pintype "passive"))
      (node (ref "R25") (pin "1") (pinfunction "1_1") (pintype "passive"))
      (node (ref "R26") (pin "2") (pinfunction "2_2") (pintype "passive"))
      (node (ref "U5") (pin "R") (pinfunction "R_R") (pintype "passive"))
    )
    (net (code "32") (name "Net-(C14-Pad2)") (class "Default")
      (node (ref "C14") (pin "2") (pinfunction "2_2") (pintype "passive"))
      (node (ref "R27") (pin "2") (pinfunction "2_2") (pintype "passive"))
      (node (ref "U5") (pin "C") (pinfunction "C_C") (pintype "passive"))
    )
    (net (code "33") (name "Net-(C20-Pad2)") (class "Default")
      (node (ref "C20") (pin "2") (pinfunction "2_2") (pintype "passive"))
      (node (ref "D6") (pin "C") (pinfunction "C_C") (pintype "passive"))
      (node (ref "R36") (pin "1") (pinfunction "1_1") (pintype "passive"))
    )
    (net (code "34") (name "Net-(C21-Pad+)") (class "Default")
      (node (ref "C21") (pin "+") (pinfunction "+_+") (pintype "passive"))
      (node (ref "D7") (pin "C") (pinfunction "C_C") (pintype "passive"))
      (node (ref "L3") (pin "1") (pinfunction "1_1") (pintype "passive"))
    )
    (net (code "35") (name "Net-(C23-Pad+)") (class "Default")
      (node (ref "C23") (pin "+") (pinfunction "+_+") (pintype "passive"))
      (node (ref "D8") (pin "C") (pinfunction "C_C") (pintype "passive"))
      (node (ref "L4") (pin "1") (pinfunction "1_1") (pintype "passive"))
    )
    (net (code "36") (name "Net-(D4-AC1)") (class "Default")
      (node (ref "C12") (pin "2") (pinfunction "2_2") (pintype "passive"))
      (node (ref "D4") (pin "AC2") (pinfunction "AC1_AC2") (pintype "passive"))
      (node (ref "L2") (pin "3") (pinfunction "4_3") (pintype "passive"))
      (node (ref "VZ2") (pin "2") (pinfunction "2_2") (pintype "passive"))
    )
    (net (code "37") (name "Net-(D4-AC2)") (class "Default")
      (node (ref "C12") (pin "1") (pinfunction "1_1") (pintype "passive"))
      (node (ref "D4") (pin "AC1") (pinfunction "AC2_AC1") (pintype "passive"))
      (node (ref "L2") (pin "2") (pinfunction "2_2") (pintype "passive"))
    )
    (net (code "38") (name "Net-(D4-Pad-)") (class "Default")
      (node (ref "D4") (pin "-") (pinfunction "-_-") (pintype "passive"))
      (node (ref "TH1") (pin "2") (pinfunction "2_2") (pintype "passive"))
    )
    (net (code "39") (name "Net-(F1-Pad1A)") (class "Default")
      (node (ref "F1") (pin "1A") (pinfunction "1A_1A") (pintype "passive"))
      (node (ref "J6") (pin "3") (pinfunction "3_3") (pintype "passive"))
    )
    (net (code "40") (name "Net-(F2-Pad2A)") (class "Default")
      (node (ref "F2") (pin "2A") (pinfunction "2A_2A") (pintype "passive"))
      (node (ref "L2") (pin "1") (pinfunction "1_1") (pintype "passive"))
    )
    (net (code "41") (name "Net-(J5-Pad1)") (class "Default")
      (node (ref "J5") (pin "1") (pinfunction "1_1") (pintype "passive"))
      (node (ref "J6") (pin "1") (pinfunction "1_1") (pintype "passive"))
    )
    (net (code "42") (name "Net-(Q1-PadB)") (class "Default")
      (node (ref "Q1") (pin "B") (pinfunction "B_B") (pintype "passive"))
      (node (ref "R17") (pin "1") (pinfunction "1_1") (pintype "passive"))
    )
    (net (code "43") (name "Net-(Q1-PadC)") (class "Default")
      (node (ref "Q1") (pin "C") (pinfunction "C_C") (pintype "passive"))
      (node (ref "R19") (pin "1") (pinfunction "1_1") (pintype "passive"))
    )
    (net (code "44") (name "Net-(Q2-A1)") (class "Default")
      (node (ref "L1") (pin "2") (pinfunction "2_2") (pintype "passive"))
      (node (ref "Q2") (pin "T1") (pinfunction "A1_T1") (pintype "passive"))
      (node (ref "R18") (pin "1") (pinfunction "1_1") (pintype "passive"))
    )
    (net (code "45") (name "Net-(Q2-A2)") (class "Default")
      (node (ref "J8") (pin "3") (pinfunction "3_3") (pintype "passive"))
      (node (ref "Q2") (pin "T2") (pinfunction "A2_T2") (pintype "passive"))
      (node (ref "R20") (pin "2") (pinfunction "2_2") (pintype "passive"))
      (node (ref "SQ1") (pin "2") (pinfunction "3_2") (pintype "passive"))
    )
    (net (code "46") (name "Net-(Q3-B)") (class "Default")
      (node (ref "Q3") (pin "2") (pinfunction "B_2") (pintype "passive"))
      (node (ref "R21") (pin "1") (pinfunction "1_1") (pintype "passive"))
    )
    (net (code "47") (name "Net-(Q3-C)") (class "Default")
      (node (ref "DP3") (pin "3") (pinfunction "CC_3") (pintype "passive"))
      (node (ref "DP3") (pin "8") (pinfunction "CC_8") (pintype "passive"))
      (node (ref "Q3") (pin "3") (pinfunction "C_3") (pintype "passive"))
    )
    (net (code "48") (name "Net-(Q4-B)") (class "Default")
      (node (ref "Q4") (pin "2") (pinfunction "B_2") (pintype "passive"))
      (node (ref "R22") (pin "1") (pinfunction "1_1") (pintype "passive"))
    )
    (net (code "49") (name "Net-(Q4-C)") (class "Default")
      (node (ref "DP2") (pin "3") (pinfunction "CC_3") (pintype "passive"))
      (node (ref "DP2") (pin "8") (pinfunction "CC_8") (pintype "passive"))
      (node (ref "Q4") (pin "3") (pinfunction "C_3") (pintype "passive"))
    )
    (net (code "50") (name "Net-(Q5-B)") (class "Default")
      (node (ref "Q5") (pin "2") (pinfunction "B_2") (pintype "passive"))
      (node (ref "R23") (pin "1") (pinfunction "1_1") (pintype "passive"))
    )
    (net (code "51") (name "Net-(Q5-C)") (class "Default")
      (node (ref "DP1") (pin "3") (pinfunction "CC_3") (pintype "passive"))
      (node (ref "DP1") (pin "8") (pinfunction "CC_8") (pintype "passive"))
      (node (ref "Q5") (pin "3") (pinfunction "C_3") (pintype "passive"))
    )
    (net (code "52") (name "Net-(Q6-PadG)") (class "Default")
      (node (ref "Q6") (pin "G") (pinfunction "G_G") (pintype "passive"))
      (node (ref "R33") (pin "1") (pinfunction "1_1") (pintype "passive"))
      (node (ref "R34") (pin "2") (pinfunction "2_2") (pintype "passive"))
    )
    (net (code "53") (name "Net-(Q6-PadS)") (class "Default")
      (node (ref "Q6") (pin "S") (pinfunction "S_S") (pintype "passive"))
      (node (ref "R32") (pin "1") (pinfunction "1_1") (pintype "passive"))
      (node (ref "R34") (pin "1") (pinfunction "1_1") (pintype "passive"))
      (node (ref "R35") (pin "2") (pinfunction "2_2") (pintype "passive"))
    )
    (net (code "54") (name "Net-(S1-P)") (class "Default")
      (node (ref "C5") (pin "1") (pinfunction "1_1") (pintype "passive"))
      (node (ref "D3") (pin "A") (pinfunction "A_A") (pintype "passive"))
      (node (ref "R14") (pin "1") (pinfunction "1_1") (pintype "passive"))
      (node (ref "S1") (pin "3") (pinfunction "P_3") (pintype "passive"))
      (node (ref "S1") (pin "4") (pinfunction "P1_4") (pintype "passive"))
      (node (ref "U2") (pin "25") (pinfunction "RB4_25") (pintype "bidirectional"))
    )
    (net (code "55") (name "Net-(T1-2)") (class "Default")
      (node (ref "D5") (pin "A") (pinfunction "A_A") (pintype "passive"))
      (node (ref "T1") (pin "3") (pinfunction "2_3") (pintype "passive"))
    )
    (net (code "56") (name "Net-(T1-4)") (class "Default")
      (node (ref "D6") (pin "A") (pinfunction "A_A") (pintype "passive"))
      (node (ref "Q6") (pin "D") (pinfunction "D_D") (pintype "passive"))
      (node (ref "T1") (pin "2") (pinfunction "4_2") (pintype "passive"))
    )
    (net (code "57") (name "Net-(T1-5)") (class "Default")
      (node (ref "D8") (pin "A2") (pinfunction "A2_A2") (pintype "passive"))
      (node (ref "T1") (pin "9") (pinfunction "5_9") (pintype "passive"))
    )
    (net (code "58") (name "Net-(T1-7)") (class "Default")
      (node (ref "D8") (pin "A1") (pinfunction "A1_A1") (pintype "passive"))
      (node (ref "T1") (pin "10") (pinfunction "7_10") (pintype "passive"))
    )
    (net (code "59") (name "Net-(T1-8)") (class "Default")
      (node (ref "D7") (pin "A2") (pinfunction "A2_A2") (pintype "passive"))
      (node (ref "T1") (pin "5") (pinfunction "8_5") (pintype "passive"))
    )
    (net (code "60") (name "Net-(T1-10)") (class "Default")
      (node (ref "D7") (pin "A1") (pinfunction "A1_A1") (pintype "passive"))
      (node (ref "T1") (pin "6") (pinfunction "10_6") (pintype "passive"))
    )
    (net (code "61") (name "Net-(U1-C{slash}R)") (class "Default")
      (node (ref "C2") (pin "1") (pinfunction "1_1") (pintype "passive"))
      (node (ref "R3") (pin "1") (pinfunction "1_1") (pintype "passive"))
      (node (ref "U1") (pin "27") (pinfunction "C/R_27") (pintype "bidirectional"))
    )
    (net (code "62") (name "Net-(U1-RSA)") (class "Default")
      (node (ref "R1") (pin "2") (pinfunction "2_2") (pintype "passive"))
      (node (ref "U1") (pin "10") (pinfunction "RSA_10") (pintype "bidirectional"))
      (node (ref "U1") (pin "3") (pinfunction "VSA_3") (pintype "bidirectional"))
    )
    (net (code "63") (name "Net-(U1-RSB)") (class "Default")
      (node (ref "R2") (pin "2") (pinfunction "2_2") (pintype "passive"))
      (node (ref "U1") (pin "18") (pinfunction "RSB_18") (pintype "bidirectional"))
      (node (ref "U1") (pin "26") (pinfunction "VSB_26") (pintype "bidirectional"))
    )
    (net (code "64") (name "Net-(U2-OSC1{slash}CLKIN)") (class "Default")
      (node (ref "C7") (pin "1") (pinfunction "1_1") (pintype "passive"))
      (node (ref "U2") (pin "9") (pinfunction "OSC1/CLKIN_9") (pintype "input"))
      (node (ref "X1") (pin "2") (pinfunction "2_2") (pintype "passive"))
    )
    (net (code "65") (name "Net-(U2-OSC2{slash}CLKOUT)") (class "Default")
      (node (ref "C6") (pin "1") (pinfunction "1_1") (pintype "passive"))
      (node (ref "U2") (pin "10") (pinfunction "OSC2/CLKOUT_10") (pintype "output"))
      (node (ref "X1") (pin "1") (pinfunction "1_1") (pintype "passive"))
    )
    (net (code "66") (name "Net-(U2-PGM{slash}RB3)") (class "Default")
      (node (ref "R5") (pin "2") (pinfunction "2_2") (pintype "passive"))
      (node (ref "U2") (pin "24") (pinfunction "PGM/RB3_24") (pintype "bidirectional"))
    )
    (net (code "67") (name "Net-(U2-VDD)") (class "Default")
      (node (ref "C8") (pin "+") (pinfunction "+_+") (pintype "passive"))
      (node (ref "C9") (pin "1") (pinfunction "1_1") (pintype "passive"))
      (node (ref "D1") (pin "C") (pinfunction "C_C") (pintype "passive"))
      (node (ref "D2") (pin "C") (pinfunction "C_C") (pintype "passive"))
      (node (ref "R6") (pin "2") (pinfunction "2_2") (pintype "passive"))
      (node (ref "U2") (pin "20") (pinfunction "VDD_20") (pintype "power_in"))
    )
    (net (code "68") (name "Net-(U3-A1)") (class "Default")
      (node (ref "Q2") (pin "G") (pinfunction "G_G") (pintype "passive"))
      (node (ref "R18") (pin "2") (pinfunction "2_2") (pintype "passive"))
      (node (ref "U3") (pin "3") (pinfunction "A1_3") (pintype "passive"))
    )
    (net (code "69") (name "Net-(U3-A2)") (class "Default")
      (node (ref "R20") (pin "1") (pinfunction "1_1") (pintype "passive"))
      (node (ref "U3") (pin "4") (pinfunction "A2_4") (pintype "passive"))
    )
    (net (code "70") (name "Net-(U3-C)") (class "Default")
      (node (ref "R19") (pin "2") (pinfunction "2_2") (pintype "passive"))
      (node (ref "U3") (pin "2") (pinfunction "C_2") (pintype "passive"))
    )
    (net (code "71") (name "Net-(U4-COMP)") (class "Default")
      (node (ref "C15") (pin "1") (pinfunction "1_1") (pintype "passive"))
      (node (ref "R30") (pin "2") (pinfunction "2_2") (pintype "passive"))
      (node (ref "U4") (pin "1") (pinfunction "COMP_1") (pintype "passive"))
    )
    (net (code "72") (name "Net-(U4-ISENSE)") (class "Default")
      (node (ref "C17") (pin "1") (pinfunction "1_1") (pintype "passive"))
      (node (ref "R32") (pin "2") (pinfunction "2_2") (pintype "passive"))
      (node (ref "U4") (pin "3") (pinfunction "ISENSE_3") (pintype "input"))
    )
    (net (code "73") (name "Net-(U4-OUT)") (class "Default")
      (node (ref "R33") (pin "2") (pinfunction "2_2") (pintype "passive"))
      (node (ref "U4") (pin "6") (pinfunction "OUT_6") (pintype "output"))
    )
    (net (code "74") (name "Net-(U4-RT{slash}CT)") (class "Default")
      (node (ref "C16") (pin "1") (pinfunction "1_1") (pintype "passive"))
      (node (ref "R31") (pin "1") (pinfunction "1_1") (pintype "passive"))
      (node (ref "U4") (pin "4") (pinfunction "RT/CT_4") (pintype "passive"))
    )
    (net (code "75") (name "Net-(U4-VCC)") (class "Default")
      (node (ref "C18") (pin "+") (pinfunction "+_+") (pintype "passive"))
      (node (ref "C19") (pin "1") (pinfunction "1_1") (pintype "passive"))
      (node (ref "D5") (pin "C") (pinfunction "C_C") (pintype "passive"))
      (node (ref "R24") (pin "1") (pinfunction "1_1") (pintype "passive"))
      (node (ref "U4") (pin "7") (pinfunction "VCC_7") (pintype "power_in"))
    )
    (net (code "76") (name "Net-(U4-VFB)") (class "Default")
      (node (ref "C15") (pin "2") (pinfunction "2_2") (pintype "passive"))
      (node (ref "R29") (pin "1") (pinfunction "1_1") (pintype "passive"))
      (node (ref "R30") (pin "1") (pinfunction "1_1") (pintype "passive"))
      (node (ref "U4") (pin "2") (pinfunction "VFB_2") (pintype "input"))
    )
    (net (code "77") (name "Net-(U4-VREF)") (class "Default")
      (node (ref "R31") (pin "2") (pinfunction "2_2") (pintype "passive"))
      (node (ref "U4") (pin "8") (pinfunction "VREF_8") (pintype "passive"))
      (node (ref "U6") (pin "4") (pinfunction "COL_4") (pintype "passive"))
    )
    (net (code "78") (name "Net-(U6-C)") (class "Default")
      (node (ref "R27") (pin "1") (pinfunction "1_1") (pintype "passive"))
      (node (ref "U6") (pin "2") (pinfunction "C_2") (pintype "passive"))
    )
    (net (code "79") (name "Net-(U6-EMIT)") (class "Default")
      (node (ref "R28") (pin "2") (pinfunction "2_2") (pintype "passive"))
      (node (ref "R29") (pin "2") (pinfunction "2_2") (pintype "passive"))
      (node (ref "U6") (pin "3") (pinfunction "EMIT_3") (pintype "passive"))
    )
    (net (code "80") (name "OUT1") (class "Default")
      (node (ref "J1") (pin "1") (pinfunction "1_1") (pintype "passive"))
      (node (ref "U1") (pin "9") (pinfunction "OUT1_9") (pintype "output"))
    )
    (net (code "81") (name "OUT2") (class "Default")
      (node (ref "J1") (pin "2") (pinfunction "2_2") (pintype "passive"))
      (node (ref "U1") (pin "11") (pinfunction "OUT2_11") (pintype "output"))
    )
    (net (code "82") (name "OUT3") (class "Default")
      (node (ref "J1") (pin "3") (pinfunction "3_3") (pintype "passive"))
      (node (ref "U1") (pin "15") (pinfunction "OUT3_15") (pintype "output"))
    )
    (net (code "83") (name "OUT4") (class "Default")
      (node (ref "J1") (pin "4") (pinfunction "4_4") (pintype "passive"))
      (node (ref "U1") (pin "19") (pinfunction "OUT4_19") (pintype "output"))
    )
    (net (code "84") (name "PGC") (class "Default")
      (node (ref "J3") (pin "5") (pinfunction "5_5") (pintype "passive"))
      (node (ref "U2") (pin "27") (pinfunction "PGC/RB6_27") (pintype "bidirectional"))
    )
    (net (code "85") (name "PGD") (class "Default")
      (node (ref "J3") (pin "4") (pinfunction "4_4") (pintype "passive"))
      (node (ref "U2") (pin "28") (pinfunction "PGD/RB7_28") (pintype "bidirectional"))
    )
    (net (code "86") (name "VDD") (class "Default")
      (node (ref "D2") (pin "A") (pinfunction "A_A") (pintype "passive"))
      (node (ref "J3") (pin "2") (pinfunction "2_2") (pintype "passive"))
    )
    (net (code "87") (name "VPP") (class "Default")
      (node (ref "J3") (pin "1") (pinfunction "1_1") (pintype "passive"))
      (node (ref "R6") (pin "1") (pinfunction "1_1") (pintype "passive"))
      (node (ref "U2") (pin "1") (pinfunction "~{MCLR/THV}_1") (pintype "input"))
    )
    (net (code "88") (name "unconnected-(DP1-DP-Pad5)") (class "Default")
      (node (ref "DP1") (pin "5") (pinfunction "DP_5") (pintype "passive"))
    )
    (net (code "89") (name "unconnected-(DP2-DP-Pad5)") (class "Default")
      (node (ref "DP2") (pin "5") (pinfunction "DP_5") (pintype "passive"))
    )
    (net (code "90") (name "unconnected-(DP3-DP-Pad5)") (class "Default")
      (node (ref "DP3") (pin "5") (pinfunction "DP_5") (pintype "passive"))
    )
    (net (code "91") (name "unconnected-(F1-Pad1B)") (class "Default")
      (node (ref "F1") (pin "1B") (pinfunction "1B_1B") (pintype "passive"))
    )
    (net (code "92") (name "unconnected-(F1-Pad2B)") (class "Default")
      (node (ref "F1") (pin "2B") (pinfunction "2B_2B") (pintype "passive"))
    )
    (net (code "93") (name "unconnected-(F2-Pad1B)") (class "Default")
      (node (ref "F2") (pin "1B") (pinfunction "1B_1B") (pintype "passive"))
    )
    (net (code "94") (name "unconnected-(F2-Pad2B)") (class "Default")
      (node (ref "F2") (pin "2B") (pinfunction "2B_2B") (pintype "passive"))
    )
    (net (code "95") (name "unconnected-(J3-Pad6)") (class "Default")
      (node (ref "J3") (pin "6") (pinfunction "6_6") (pintype "passive"))
    )
    (net (code "96") (name "unconnected-(J5-Pad2)") (class "Default")
      (node (ref "J5") (pin "2") (pinfunction "2_2") (pintype "passive"))
    )
    (net (code "97") (name "unconnected-(J6-Pad2)") (class "Default")
      (node (ref "J6") (pin "2") (pinfunction "2_2") (pintype "passive"))
    )
    (net (code "98") (name "unconnected-(J8-Pad2)") (class "Default")
      (node (ref "J8") (pin "2") (pinfunction "2_2") (pintype "passive"))
    )
    (net (code "99") (name "unconnected-(U2-RA4{slash}T0CKI-Pad6)") (class "Default")
      (node (ref "U2") (pin "6") (pinfunction "RA4/T0CKI_6") (pintype "bidirectional"))
    )
    (net (code "100") (name "unconnected-(U2-RX{slash}RC7-Pad18)") (class "Default")
      (node (ref "U2") (pin "18") (pinfunction "RX/RC7_18") (pintype "bidirectional"))
    )
  )
)
